# T09_LockBox_ver5_0.net
KiCad netlist of a schematic drawn in EAGLE
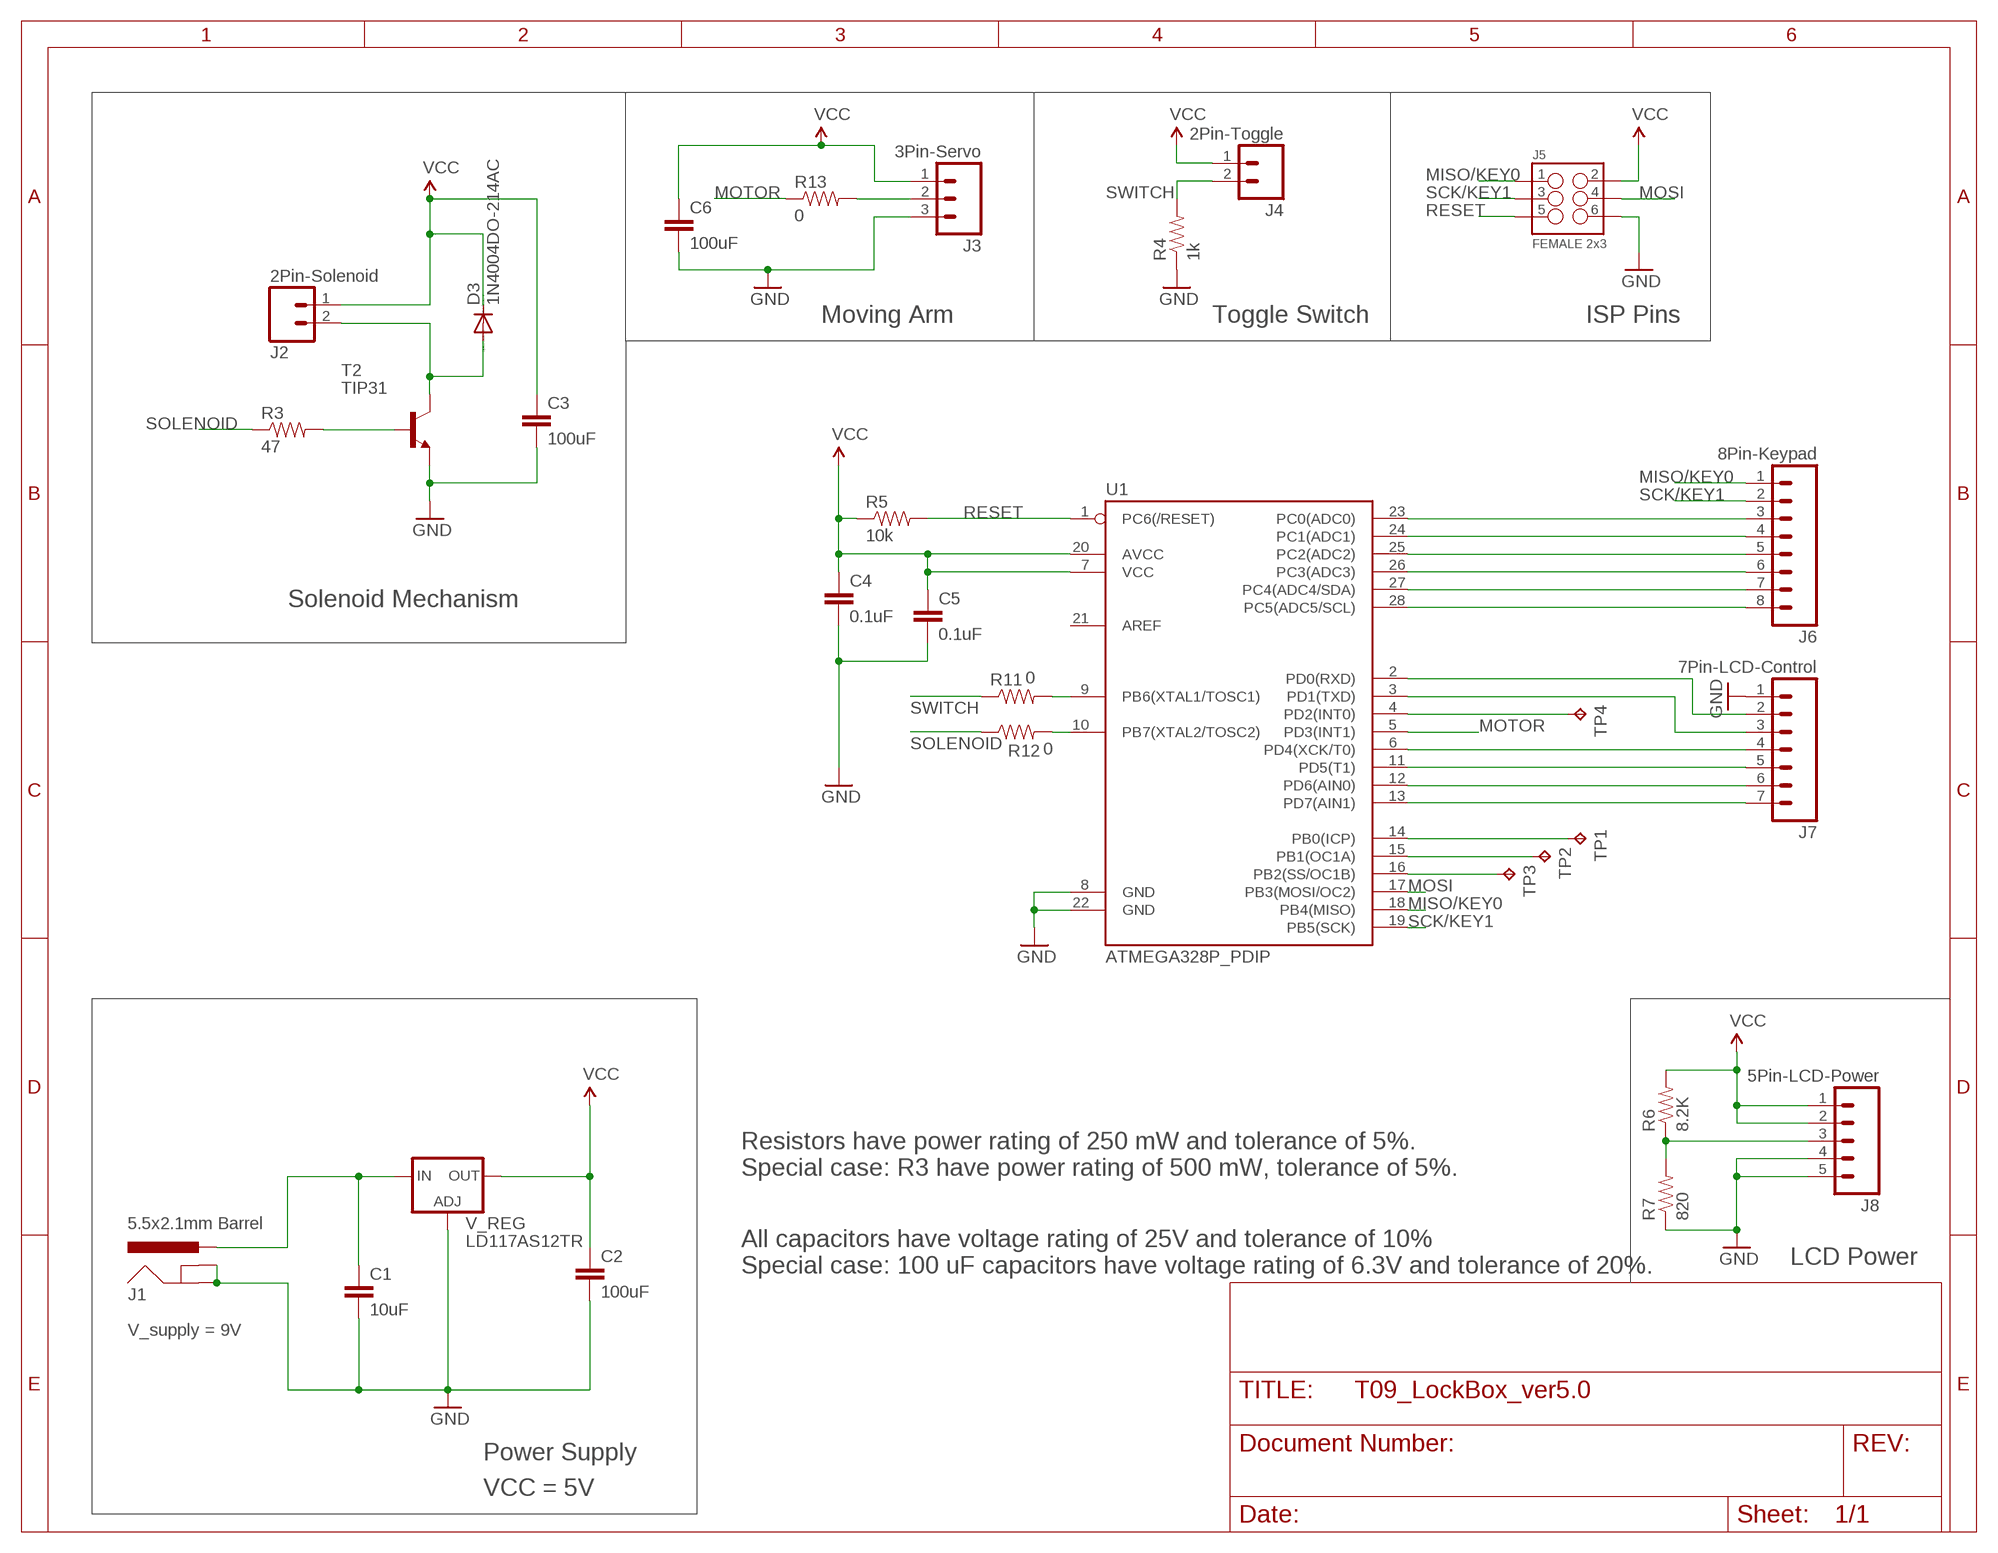
[diagram p0: schematic, sheet 1]

(export (version "E")
  (design (tool "Eeschema 10.0.6"))
  (components
    (comp (ref "C1")
      (value "10uF")
      (footprint "eagle-import:0603-CAP")
      (libsource (lib "eagle-import") (part "CAP0603-CAP"))
    )
    (comp (ref "C2")
      (value "100uF")
      (footprint "eagle-import:0603-CAP")
      (libsource (lib "eagle-import") (part "CAP0603-CAP"))
    )
    (comp (ref "C3")
      (value "100uF")
      (footprint "eagle-import:0603-CAP")
      (libsource (lib "eagle-import") (part "CAP0603-CAP"))
    )
    (comp (ref "C4")
      (value "0.1uF")
      (footprint "eagle-import:0603-CAP")
      (libsource (lib "eagle-import") (part "CAP0603-CAP"))
    )
    (comp (ref "C5")
      (value "0.1uF")
      (footprint "eagle-import:0603-CAP")
      (libsource (lib "eagle-import") (part "CAP0603-CAP"))
    )
    (comp (ref "C6")
      (value "100uF")
      (footprint "eagle-import:0603-CAP")
      (libsource (lib "eagle-import") (part "CAP0603-CAP"))
    )
    (comp (ref "D3")
      (value "1N4004DO-214AC")
      (footprint "eagle-import:DO-214AC")
      (libsource (lib "eagle-import") (part "1N4004DO-214AC"))
    )
    (comp (ref "J1")
      (value "5.5x2.1mm Barrel")
      (footprint "eagle-import:POWER_JACK_SMD")
      (libsource (lib "eagle-import") (part "POWER_JACKSMD"))
    )
    (comp (ref "J2")
      (value "2Pin-Solenoid")
      (footprint "eagle-import:1X02")
      (libsource (lib "eagle-import") (part "M02PTH"))
    )
    (comp (ref "J3")
      (value "3Pin-Servo")
      (footprint "eagle-import:1X03")
      (libsource (lib "eagle-import") (part "M03PTH"))
    )
    (comp (ref "J4")
      (value "2Pin-Toggle")
      (footprint "eagle-import:1X02")
      (libsource (lib "eagle-import") (part "M02PTH"))
    )
    (comp (ref "J5")
      (value "FEMALE 2x3")
      (footprint "eagle-import:2X3")
      (libsource (lib "eagle-import") (part "M03X2FEMALE"))
    )
    (comp (ref "J6")
      (value "8Pin-Keypad")
      (footprint "eagle-import:1X08_ROUND")
      (libsource (lib "eagle-import") (part "M08"))
    )
    (comp (ref "J7")
      (value "7Pin-LCD-Control")
      (footprint "eagle-import:1X07")
      (libsource (lib "eagle-import") (part "M07"))
    )
    (comp (ref "J8")
      (value "5Pin-LCD-Power")
      (footprint "eagle-import:1X05")
      (libsource (lib "eagle-import") (part "M05PTH"))
    )
    (comp (ref "R3")
      (value "47")
      (footprint "eagle-import:0805")
      (libsource (lib "eagle-import") (part "RESISTOR0805-RES"))
    )
    (comp (ref "R4")
      (value "1k")
      (footprint "eagle-import:0603-RES")
      (libsource (lib "eagle-import") (part "RESISTOR0603"))
    )
    (comp (ref "R5")
      (value "10k")
      (footprint "eagle-import:0603-RES")
      (libsource (lib "eagle-import") (part "RESISTOR0603"))
    )
    (comp (ref "R6")
      (value "8.2K")
      (footprint "eagle-import:0603-RES")
      (libsource (lib "eagle-import") (part "RESISTOR0603"))
    )
    (comp (ref "R7")
      (value "820")
      (footprint "eagle-import:0603-RES")
      (libsource (lib "eagle-import") (part "RESISTOR0603"))
    )
    (comp (ref "R11")
      (value "0")
      (footprint "eagle-import:0603-RES")
      (libsource (lib "eagle-import") (part "RESISTOR0603"))
    )
    (comp (ref "R12")
      (value "0")
      (footprint "eagle-import:0603-RES")
      (libsource (lib "eagle-import") (part "RESISTOR0603"))
    )
    (comp (ref "R13")
      (value "0")
      (footprint "eagle-import:0603-RES")
      (libsource (lib "eagle-import") (part "RESISTOR0603"))
    )
    (comp (ref "T2")
      (value "TIP31")
      (footprint "eagle-import:TO220")
      (libsource (lib "eagle-import") (part "TIP31"))
    )
    (comp (ref "TP1")
      (value "TPPAD1-13")
      (footprint "eagle-import:P1-13")
      (libsource (lib "eagle-import") (part "TPPAD1-13"))
    )
    (comp (ref "TP2")
      (value "TPPAD1-13")
      (footprint "eagle-import:P1-13")
      (libsource (lib "eagle-import") (part "TPPAD1-13"))
    )
    (comp (ref "TP3")
      (value "TPPAD1-13")
      (footprint "eagle-import:P1-13")
      (libsource (lib "eagle-import") (part "TPPAD1-13"))
    )
    (comp (ref "TP4")
      (value "TPPAD1-13")
      (footprint "eagle-import:P1-13")
      (libsource (lib "eagle-import") (part "TPPAD1-13"))
    )
    (comp (ref "U1")
      (value "ATMEGA328P_PDIP")
      (footprint "eagle-import:DIL28-3")
      (libsource (lib "eagle-import") (part "ATMEGA328P_PDIP"))
    )
    (comp (ref "V_REG")
      (value "LD117AS12TR")
      (footprint "eagle-import:SOT223")
      (libsource (lib "eagle-import") (part "LD117A?S12TR"))
    )
  )
  (nets
    (net (code "1") (name "/MISO{slash}KEY0") (class "Default")
      (node (ref "J5") (pin "1") (pinfunction "1_1") (pintype "bidirectional"))
      (node (ref "J6") (pin "1") (pinfunction "1_1") (pintype "passive"))
      (node (ref "U1") (pin "18") (pinfunction "PB4(MISO)_18") (pintype "bidirectional"))
    )
    (net (code "2") (name "/MOSI") (class "Default")
      (node (ref "J5") (pin "4") (pinfunction "4_4") (pintype "bidirectional"))
      (node (ref "U1") (pin "17") (pinfunction "PB3(MOSI/OC2)_17") (pintype "bidirectional"))
    )
    (net (code "3") (name "/MOTOR") (class "Default")
      (node (ref "R13") (pin "1") (pinfunction "1_1") (pintype "passive"))
      (node (ref "U1") (pin "5") (pinfunction "PD3(INT1)_5") (pintype "bidirectional"))
    )
    (net (code "4") (name "/RESET") (class "Default")
      (node (ref "J5") (pin "5") (pinfunction "5_5") (pintype "bidirectional"))
      (node (ref "R5") (pin "2") (pinfunction "2_2") (pintype "passive"))
      (node (ref "U1") (pin "1") (pinfunction "PC6(/RESET)_1") (pintype "bidirectional"))
    )
    (net (code "5") (name "/SCK{slash}KEY1") (class "Default")
      (node (ref "J5") (pin "3") (pinfunction "3_3") (pintype "bidirectional"))
      (node (ref "J6") (pin "2") (pinfunction "2_2") (pintype "passive"))
      (node (ref "U1") (pin "19") (pinfunction "PB5(SCK)_19") (pintype "bidirectional"))
    )
    (net (code "6") (name "/SOLENOID") (class "Default")
      (node (ref "R12") (pin "1") (pinfunction "1_1") (pintype "passive"))
      (node (ref "R3") (pin "1") (pinfunction "1_1") (pintype "passive"))
    )
    (net (code "7") (name "/SWITCH") (class "Default")
      (node (ref "J4") (pin "2") (pinfunction "2_2") (pintype "passive"))
      (node (ref "R11") (pin "1") (pinfunction "1_1") (pintype "passive"))
      (node (ref "R4") (pin "2") (pinfunction "2_2") (pintype "passive"))
    )
    (net (code "8") (name "GND") (class "Default")
      (node (ref "C1") (pin "2") (pinfunction "2_2") (pintype "passive"))
      (node (ref "C2") (pin "2") (pinfunction "2_2") (pintype "passive"))
      (node (ref "C3") (pin "2") (pinfunction "2_2") (pintype "passive"))
      (node (ref "C4") (pin "2") (pinfunction "2_2") (pintype "passive"))
      (node (ref "C5") (pin "2") (pinfunction "2_2") (pintype "passive"))
      (node (ref "C6") (pin "2") (pinfunction "2_2") (pintype "passive"))
      (node (ref "J1") (pin "GND") (pinfunction "GNDBREAK_GND") (pintype "bidirectional"))
      (node (ref "J1") (pin "P$4") (pinfunction "GND_P$4") (pintype "bidirectional"))
      (node (ref "J3") (pin "3") (pinfunction "3_3") (pintype "passive"))
      (node (ref "J5") (pin "6") (pinfunction "6_6") (pintype "bidirectional"))
      (node (ref "J7") (pin "1") (pinfunction "1_1") (pintype "passive"))
      (node (ref "J8") (pin "4") (pinfunction "4_4") (pintype "passive"))
      (node (ref "J8") (pin "5") (pinfunction "5_5") (pintype "passive"))
      (node (ref "R4") (pin "1") (pinfunction "1_1") (pintype "passive"))
      (node (ref "R7") (pin "1") (pinfunction "1_1") (pintype "passive"))
      (node (ref "T2") (pin "3") (pinfunction "E_3") (pintype "passive"))
      (node (ref "U1") (pin "22") (pinfunction "GND_22") (pintype "bidirectional"))
      (node (ref "U1") (pin "8") (pinfunction "GND_8") (pintype "bidirectional"))
      (node (ref "V_REG") (pin "1") (pinfunction "ADJ_1") (pintype "input"))
    )
    (net (code "9") (name "Net-(J1-PWR)") (class "Default")
      (node (ref "C1") (pin "1") (pinfunction "1_1") (pintype "passive"))
      (node (ref "J1") (pin "VIN0") (pinfunction "PWR_VIN0") (pintype "bidirectional"))
      (node (ref "V_REG") (pin "3") (pinfunction "IN_3") (pintype "input"))
    )
    (net (code "10") (name "Net-(J3-Pad2)") (class "Default")
      (node (ref "J3") (pin "2") (pinfunction "2_2") (pintype "passive"))
      (node (ref "R13") (pin "2") (pinfunction "2_2") (pintype "passive"))
    )
    (net (code "11") (name "Net-(J8-Pad3)") (class "Default")
      (node (ref "J8") (pin "3") (pinfunction "3_3") (pintype "passive"))
      (node (ref "R6") (pin "1") (pinfunction "1_1") (pintype "passive"))
      (node (ref "R7") (pin "2") (pinfunction "2_2") (pintype "passive"))
    )
    (net (code "12") (name "Net-(T2-B)") (class "Default")
      (node (ref "R3") (pin "2") (pinfunction "2_2") (pintype "passive"))
      (node (ref "T2") (pin "1") (pinfunction "B_1") (pintype "passive"))
    )
    (net (code "13") (name "Net-(T2-C)") (class "Default")
      (node (ref "D3") (pin "A") (pinfunction "A_A") (pintype "passive"))
      (node (ref "J2") (pin "2") (pinfunction "2_2") (pintype "passive"))
      (node (ref "T2") (pin "2") (pinfunction "C_2") (pintype "passive"))
    )
    (net (code "14") (name "Net-(U1-PB0(ICP))") (class "Default")
      (node (ref "TP1") (pin "TP") (pinfunction "TP_TP") (pintype "input"))
      (node (ref "U1") (pin "14") (pinfunction "PB0(ICP)_14") (pintype "bidirectional"))
    )
    (net (code "15") (name "Net-(U1-PB1(OC1A))") (class "Default")
      (node (ref "TP2") (pin "TP") (pinfunction "TP_TP") (pintype "input"))
      (node (ref "U1") (pin "15") (pinfunction "PB1(OC1A)_15") (pintype "bidirectional"))
    )
    (net (code "16") (name "Net-(U1-PB2(SS{slash}OC1B))") (class "Default")
      (node (ref "TP3") (pin "TP") (pinfunction "TP_TP") (pintype "input"))
      (node (ref "U1") (pin "16") (pinfunction "PB2(SS/OC1B)_16") (pintype "bidirectional"))
    )
    (net (code "17") (name "Net-(U1-PB6(XTAL1{slash}TOSC1))") (class "Default")
      (node (ref "R11") (pin "2") (pinfunction "2_2") (pintype "passive"))
      (node (ref "U1") (pin "9") (pinfunction "PB6(XTAL1/TOSC1)_9") (pintype "bidirectional"))
    )
    (net (code "18") (name "Net-(U1-PB7(XTAL2{slash}TOSC2))") (class "Default")
      (node (ref "R12") (pin "2") (pinfunction "2_2") (pintype "passive"))
      (node (ref "U1") (pin "10") (pinfunction "PB7(XTAL2/TOSC2)_10") (pintype "bidirectional"))
    )
    (net (code "19") (name "Net-(U1-PC0(ADC0))") (class "Default")
      (node (ref "J6") (pin "3") (pinfunction "3_3") (pintype "passive"))
      (node (ref "U1") (pin "23") (pinfunction "PC0(ADC0)_23") (pintype "bidirectional"))
    )
    (net (code "20") (name "Net-(U1-PC1(ADC1))") (class "Default")
      (node (ref "J6") (pin "4") (pinfunction "4_4") (pintype "passive"))
      (node (ref "U1") (pin "24") (pinfunction "PC1(ADC1)_24") (pintype "bidirectional"))
    )
    (net (code "21") (name "Net-(U1-PC2(ADC2))") (class "Default")
      (node (ref "J6") (pin "5") (pinfunction "5_5") (pintype "passive"))
      (node (ref "U1") (pin "25") (pinfunction "PC2(ADC2)_25") (pintype "bidirectional"))
    )
    (net (code "22") (name "Net-(U1-PC3(ADC3))") (class "Default")
      (node (ref "J6") (pin "6") (pinfunction "6_6") (pintype "passive"))
      (node (ref "U1") (pin "26") (pinfunction "PC3(ADC3)_26") (pintype "bidirectional"))
    )
    (net (code "23") (name "Net-(U1-PC4(ADC4{slash}SDA))") (class "Default")
      (node (ref "J6") (pin "7") (pinfunction "7_7") (pintype "passive"))
      (node (ref "U1") (pin "27") (pinfunction "PC4(ADC4/SDA)_27") (pintype "bidirectional"))
    )
    (net (code "24") (name "Net-(U1-PC5(ADC5{slash}SCL))") (class "Default")
      (node (ref "J6") (pin "8") (pinfunction "8_8") (pintype "passive"))
      (node (ref "U1") (pin "28") (pinfunction "PC5(ADC5/SCL)_28") (pintype "bidirectional"))
    )
    (net (code "25") (name "Net-(U1-PD0(RXD))") (class "Default")
      (node (ref "J7") (pin "2") (pinfunction "2_2") (pintype "passive"))
      (node (ref "U1") (pin "2") (pinfunction "PD0(RXD)_2") (pintype "bidirectional"))
    )
    (net (code "26") (name "Net-(U1-PD1(TXD))") (class "Default")
      (node (ref "J7") (pin "3") (pinfunction "3_3") (pintype "passive"))
      (node (ref "U1") (pin "3") (pinfunction "PD1(TXD)_3") (pintype "bidirectional"))
    )
    (net (code "27") (name "Net-(U1-PD2(INT0))") (class "Default")
      (node (ref "TP4") (pin "TP") (pinfunction "TP_TP") (pintype "input"))
      (node (ref "U1") (pin "4") (pinfunction "PD2(INT0)_4") (pintype "bidirectional"))
    )
    (net (code "28") (name "Net-(U1-PD4(XCK{slash}T0))") (class "Default")
      (node (ref "J7") (pin "4") (pinfunction "4_4") (pintype "passive"))
      (node (ref "U1") (pin "6") (pinfunction "PD4(XCK/T0)_6") (pintype "bidirectional"))
    )
    (net (code "29") (name "Net-(U1-PD5(T1))") (class "Default")
      (node (ref "J7") (pin "5") (pinfunction "5_5") (pintype "passive"))
      (node (ref "U1") (pin "11") (pinfunction "PD5(T1)_11") (pintype "bidirectional"))
    )
    (net (code "30") (name "Net-(U1-PD6(AIN0))") (class "Default")
      (node (ref "J7") (pin "6") (pinfunction "6_6") (pintype "passive"))
      (node (ref "U1") (pin "12") (pinfunction "PD6(AIN0)_12") (pintype "bidirectional"))
    )
    (net (code "31") (name "Net-(U1-PD7(AIN1))") (class "Default")
      (node (ref "J7") (pin "7") (pinfunction "7_7") (pintype "passive"))
      (node (ref "U1") (pin "13") (pinfunction "PD7(AIN1)_13") (pintype "bidirectional"))
    )
    (net (code "32") (name "VCC") (class "Default")
      (node (ref "C2") (pin "1") (pinfunction "1_1") (pintype "passive"))
      (node (ref "C3") (pin "1") (pinfunction "1_1") (pintype "passive"))
      (node (ref "C4") (pin "1") (pinfunction "1_1") (pintype "passive"))
      (node (ref "C5") (pin "1") (pinfunction "1_1") (pintype "passive"))
      (node (ref "C6") (pin "1") (pinfunction "1_1") (pintype "passive"))
      (node (ref "D3") (pin "C") (pinfunction "C_C") (pintype "passive"))
      (node (ref "J2") (pin "1") (pinfunction "1_1") (pintype "passive"))
      (node (ref "J3") (pin "1") (pinfunction "1_1") (pintype "passive"))
      (node (ref "J4") (pin "1") (pinfunction "1_1") (pintype "passive"))
      (node (ref "J5") (pin "2") (pinfunction "2_2") (pintype "bidirectional"))
      (node (ref "J8") (pin "1") (pinfunction "1_1") (pintype "passive"))
      (node (ref "J8") (pin "2") (pinfunction "2_2") (pintype "passive"))
      (node (ref "R5") (pin "1") (pinfunction "1_1") (pintype "passive"))
      (node (ref "R6") (pin "2") (pinfunction "2_2") (pintype "passive"))
      (node (ref "U1") (pin "20") (pinfunction "AVCC_20") (pintype "bidirectional"))
      (node (ref "U1") (pin "7") (pinfunction "VCC_7") (pintype "bidirectional"))
      (node (ref "V_REG") (pin "4") (pinfunction "OUT_4") (pintype "passive"))
    )
    (net (code "33") (name "unconnected-(U1-AREF-Pad21)") (class "Default")
      (node (ref "U1") (pin "21") (pinfunction "AREF_21") (pintype "bidirectional"))
    )
  )
)
